# Adafruit_3_5in_480x320_FeatherWing_Capac.net
KiCad netlist of a schematic drawn in EAGLE
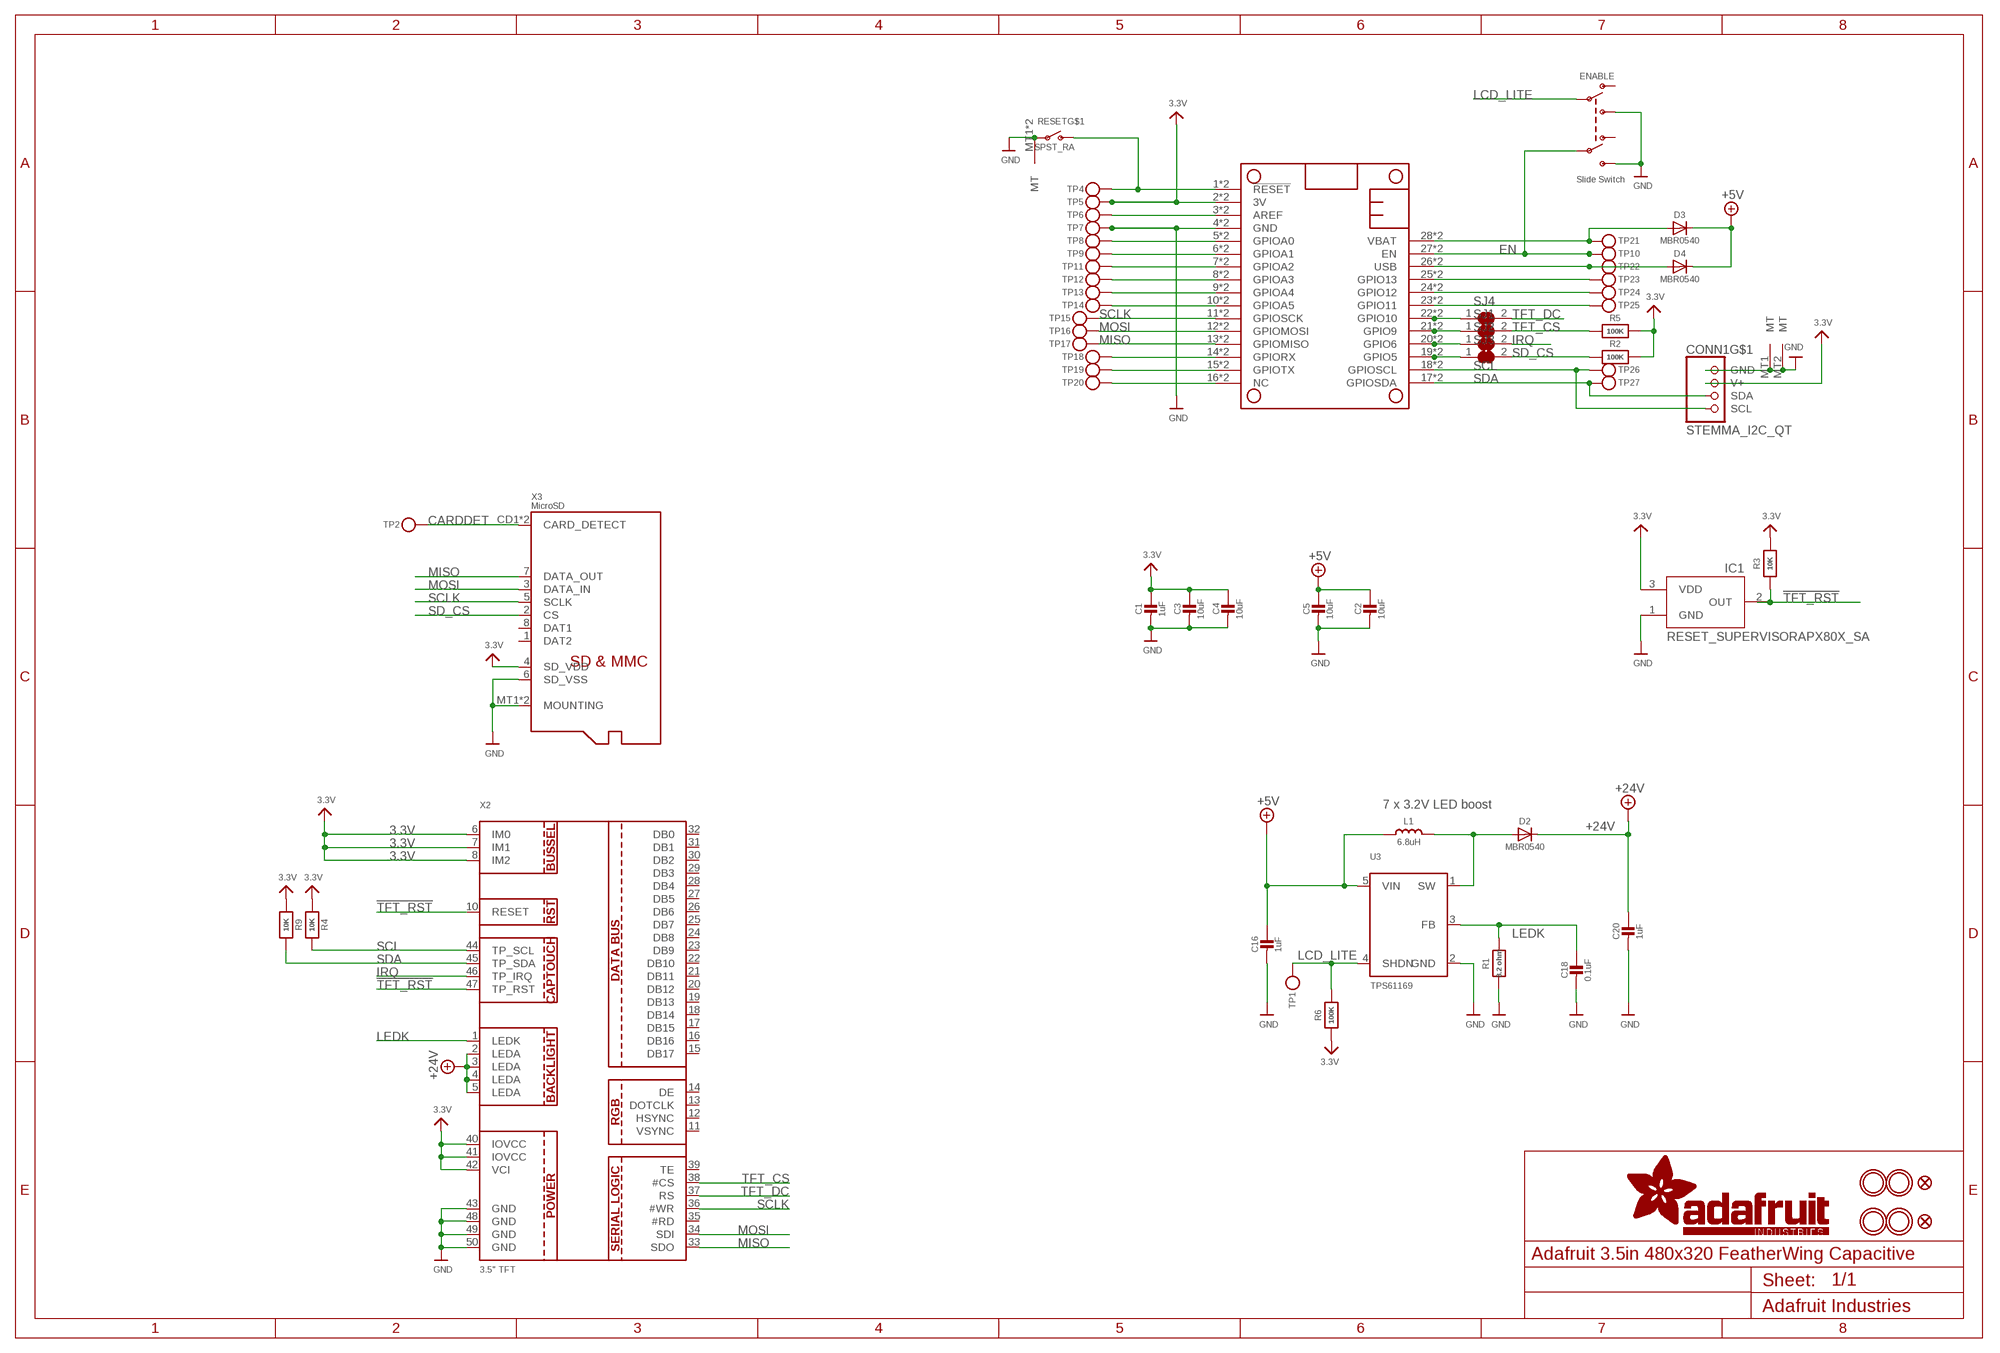
[diagram p0: schematic, sheet 1]

(export (version "E")
  (design (tool "Eeschema 10.0.6"))
  (components
    (comp (ref "C1")
      (value "1uF")
      (footprint "eagle-import:0805-NO")
      (libsource (lib "eagle-import") (part "CAP_CERAMIC0805-NOOUTLINE"))
    )
    (comp (ref "C2")
      (value "10uF")
      (footprint "eagle-import:0805-NO")
      (libsource (lib "eagle-import") (part "CAP_CERAMIC0805-NOOUTLINE"))
    )
    (comp (ref "C3")
      (value "10uF")
      (footprint "eagle-import:0805-NO")
      (libsource (lib "eagle-import") (part "CAP_CERAMIC0805-NOOUTLINE"))
    )
    (comp (ref "C4")
      (value "10uF")
      (footprint "eagle-import:0805-NO")
      (libsource (lib "eagle-import") (part "CAP_CERAMIC0805-NOOUTLINE"))
    )
    (comp (ref "C5")
      (value "10uF")
      (footprint "eagle-import:0805-NO")
      (libsource (lib "eagle-import") (part "CAP_CERAMIC0805-NOOUTLINE"))
    )
    (comp (ref "C16")
      (value "1uF")
      (footprint "eagle-import:0805-NO")
      (libsource (lib "eagle-import") (part "CAP_CERAMIC0805-NOOUTLINE"))
    )
    (comp (ref "C18")
      (value "0.1uF")
      (footprint "eagle-import:0603-NO")
      (libsource (lib "eagle-import") (part "CAP_CERAMIC0603_NO"))
    )
    (comp (ref "C20")
      (value "1uF")
      (footprint "eagle-import:0805-NO")
      (libsource (lib "eagle-import") (part "CAP_CERAMIC0805-NOOUTLINE"))
    )
    (comp (ref "CONN1")
      (value "STEMMA_I2C_QT")
      (footprint "eagle-import:JST_SH4")
      (libsource (lib "eagle-import") (part "STEMMA_I2C_QT"))
    )
    (comp (ref "D2")
      (value "MBR0540")
      (footprint "eagle-import:SOD-123")
      (libsource (lib "eagle-import") (part "DIODESOD-123"))
    )
    (comp (ref "D3")
      (value "MBR0540")
      (footprint "eagle-import:SOD-123")
      (libsource (lib "eagle-import") (part "DIODESOD-123"))
    )
    (comp (ref "D4")
      (value "MBR0540")
      (footprint "eagle-import:SOD-123")
      (libsource (lib "eagle-import") (part "DIODESOD-123"))
    )
    (comp (ref "ENABLE")
      (value "Slide Switch")
      (footprint "eagle-import:EG1390")
      (libsource (lib "eagle-import") (part "SWITCH_DPDTEG1390"))
    )
    (comp (ref "IC1")
      (value "RESET_SUPERVISORAPX80X_SA")
      (footprint "eagle-import:SOT23-WIDE")
      (libsource (lib "eagle-import") (part "RESET_SUPERVISORAPX80X_SA"))
    )
    (comp (ref "L1")
      (value "6.8uH")
      (footprint "eagle-import:INDUCTOR_5X5MM_NR5040_NOTHERMALS")
      (libsource (lib "eagle-import") (part "INDUCTORNR5040"))
    )
    (comp (ref "MS2")
      (value "FEATHERWING_SMTDUAL")
      (footprint "eagle-import:FEATHERWING_SMT2")
      (libsource (lib "eagle-import") (part "FEATHERWING_SMTDUAL"))
    )
    (comp (ref "R1")
      (value "8.2 ohm")
      (footprint "eagle-import:0603-NO")
      (libsource (lib "eagle-import") (part "RESISTOR_0603_NOOUT"))
    )
    (comp (ref "R2")
      (value "100K")
      (footprint "eagle-import:0603-NO")
      (libsource (lib "eagle-import") (part "RESISTOR_0603_NOOUT"))
    )
    (comp (ref "R3")
      (value "10K")
      (footprint "eagle-import:0603-NO")
      (libsource (lib "eagle-import") (part "RESISTOR_0603_NOOUT"))
    )
    (comp (ref "R4")
      (value "10K")
      (footprint "eagle-import:0603-NO")
      (libsource (lib "eagle-import") (part "RESISTOR_0603_NOOUT"))
    )
    (comp (ref "R5")
      (value "100K")
      (footprint "eagle-import:0603-NO")
      (libsource (lib "eagle-import") (part "RESISTOR_0603_NOOUT"))
    )
    (comp (ref "R6")
      (value "100K")
      (footprint "eagle-import:0603-NO")
      (libsource (lib "eagle-import") (part "RESISTOR_0603_NOOUT"))
    )
    (comp (ref "R9")
      (value "10K")
      (footprint "eagle-import:0603-NO")
      (libsource (lib "eagle-import") (part "RESISTOR_0603_NOOUT"))
    )
    (comp (ref "RESET")
      (value "SPST_RA")
      (footprint "eagle-import:SPST_TACTILE_RA")
      (libsource (lib "eagle-import") (part "SWITCH_SPST_MNT_TACT_RA"))
    )
    (comp (ref "SJ1")
      (value "SOLDERJUMPER_CLOSED")
      (footprint "eagle-import:SOLDERJUMPER_CLOSEDWIRE")
      (libsource (lib "eagle-import") (part "SOLDERJUMPER_CLOSED"))
    )
    (comp (ref "SJ2")
      (value "SOLDERJUMPER_CLOSED")
      (footprint "eagle-import:SOLDERJUMPER_CLOSEDWIRE")
      (libsource (lib "eagle-import") (part "SOLDERJUMPER_CLOSED"))
    )
    (comp (ref "SJ3")
      (value "SOLDERJUMPER_CLOSED")
      (footprint "eagle-import:SOLDERJUMPER_CLOSEDWIRE")
      (libsource (lib "eagle-import") (part "SOLDERJUMPER_CLOSED"))
    )
    (comp (ref "SJ4")
      (value "SOLDERJUMPER_CLOSED")
      (footprint "eagle-import:SOLDERJUMPER_CLOSEDWIRE")
      (libsource (lib "eagle-import") (part "SOLDERJUMPER_CLOSED"))
    )
    (comp (ref "TP1")
      (value "TESTPOINTPAD2MM")
      (footprint "eagle-import:TESTPOINT_PAD_2MM")
      (libsource (lib "eagle-import") (part "TESTPOINTPAD2MM"))
    )
    (comp (ref "TP2")
      (value "TESTPOINTPAD2MM")
      (footprint "eagle-import:TESTPOINT_PAD_2MM")
      (libsource (lib "eagle-import") (part "TESTPOINTPAD2MM"))
    )
    (comp (ref "TP4")
      (value "TESTPOINTPAD2MM")
      (footprint "eagle-import:TESTPOINT_PAD_2MM")
      (libsource (lib "eagle-import") (part "TESTPOINTPAD2MM"))
    )
    (comp (ref "TP5")
      (value "TESTPOINTPAD2MM")
      (footprint "eagle-import:TESTPOINT_PAD_2MM")
      (libsource (lib "eagle-import") (part "TESTPOINTPAD2MM"))
    )
    (comp (ref "TP6")
      (value "TESTPOINTPAD2MM")
      (footprint "eagle-import:TESTPOINT_PAD_2MM")
      (libsource (lib "eagle-import") (part "TESTPOINTPAD2MM"))
    )
    (comp (ref "TP7")
      (value "TESTPOINTPAD2MM")
      (footprint "eagle-import:TESTPOINT_PAD_2MM")
      (libsource (lib "eagle-import") (part "TESTPOINTPAD2MM"))
    )
    (comp (ref "TP8")
      (value "TESTPOINTPAD2MM")
      (footprint "eagle-import:TESTPOINT_PAD_2MM")
      (libsource (lib "eagle-import") (part "TESTPOINTPAD2MM"))
    )
    (comp (ref "TP9")
      (value "TESTPOINTPAD2MM")
      (footprint "eagle-import:TESTPOINT_PAD_2MM")
      (libsource (lib "eagle-import") (part "TESTPOINTPAD2MM"))
    )
    (comp (ref "TP10")
      (value "TESTPOINTPAD2MM")
      (footprint "eagle-import:TESTPOINT_PAD_2MM")
      (libsource (lib "eagle-import") (part "TESTPOINTPAD2MM"))
    )
    (comp (ref "TP11")
      (value "TESTPOINTPAD2MM")
      (footprint "eagle-import:TESTPOINT_PAD_2MM")
      (libsource (lib "eagle-import") (part "TESTPOINTPAD2MM"))
    )
    (comp (ref "TP12")
      (value "TESTPOINTPAD2MM")
      (footprint "eagle-import:TESTPOINT_PAD_2MM")
      (libsource (lib "eagle-import") (part "TESTPOINTPAD2MM"))
    )
    (comp (ref "TP13")
      (value "TESTPOINTPAD2MM")
      (footprint "eagle-import:TESTPOINT_PAD_2MM")
      (libsource (lib "eagle-import") (part "TESTPOINTPAD2MM"))
    )
    (comp (ref "TP14")
      (value "TESTPOINTPAD2MM")
      (footprint "eagle-import:TESTPOINT_PAD_2MM")
      (libsource (lib "eagle-import") (part "TESTPOINTPAD2MM"))
    )
    (comp (ref "TP15")
      (value "TESTPOINTPAD2MM")
      (footprint "eagle-import:TESTPOINT_PAD_2MM")
      (libsource (lib "eagle-import") (part "TESTPOINTPAD2MM"))
    )
    (comp (ref "TP16")
      (value "TESTPOINTPAD2MM")
      (footprint "eagle-import:TESTPOINT_PAD_2MM")
      (libsource (lib "eagle-import") (part "TESTPOINTPAD2MM"))
    )
    (comp (ref "TP17")
      (value "TESTPOINTPAD2MM")
      (footprint "eagle-import:TESTPOINT_PAD_2MM")
      (libsource (lib "eagle-import") (part "TESTPOINTPAD2MM"))
    )
    (comp (ref "TP18")
      (value "TESTPOINTPAD2MM")
      (footprint "eagle-import:TESTPOINT_PAD_2MM")
      (libsource (lib "eagle-import") (part "TESTPOINTPAD2MM"))
    )
    (comp (ref "TP19")
      (value "TESTPOINTPAD2MM")
      (footprint "eagle-import:TESTPOINT_PAD_2MM")
      (libsource (lib "eagle-import") (part "TESTPOINTPAD2MM"))
    )
    (comp (ref "TP20")
      (value "TESTPOINTPAD2MM")
      (footprint "eagle-import:TESTPOINT_PAD_2MM")
      (libsource (lib "eagle-import") (part "TESTPOINTPAD2MM"))
    )
    (comp (ref "TP21")
      (value "TESTPOINTPAD2MM")
      (footprint "eagle-import:TESTPOINT_PAD_2MM")
      (libsource (lib "eagle-import") (part "TESTPOINTPAD2MM"))
    )
    (comp (ref "TP22")
      (value "TESTPOINTPAD2MM")
      (footprint "eagle-import:TESTPOINT_PAD_2MM")
      (libsource (lib "eagle-import") (part "TESTPOINTPAD2MM"))
    )
    (comp (ref "TP23")
      (value "TESTPOINTPAD2MM")
      (footprint "eagle-import:TESTPOINT_PAD_2MM")
      (libsource (lib "eagle-import") (part "TESTPOINTPAD2MM"))
    )
    (comp (ref "TP24")
      (value "TESTPOINTPAD2MM")
      (footprint "eagle-import:TESTPOINT_PAD_2MM")
      (libsource (lib "eagle-import") (part "TESTPOINTPAD2MM"))
    )
    (comp (ref "TP25")
      (value "TESTPOINTPAD2MM")
      (footprint "eagle-import:TESTPOINT_PAD_2MM")
      (libsource (lib "eagle-import") (part "TESTPOINTPAD2MM"))
    )
    (comp (ref "TP26")
      (value "TESTPOINTPAD2MM")
      (footprint "eagle-import:TESTPOINT_PAD_2MM")
      (libsource (lib "eagle-import") (part "TESTPOINTPAD2MM"))
    )
    (comp (ref "TP27")
      (value "TESTPOINTPAD2MM")
      (footprint "eagle-import:TESTPOINT_PAD_2MM")
      (libsource (lib "eagle-import") (part "TESTPOINTPAD2MM"))
    )
    (comp (ref "U$7")
      (value "MOUNTINGHOLE3.0THIN")
      (footprint "eagle-import:MOUNTINGHOLE_3.0_PLATEDTHIN")
      (libsource (lib "eagle-import") (part "MOUNTINGHOLE3.0THIN"))
    )
    (comp (ref "U$9")
      (value "FIDUCIAL_1MM")
      (footprint "eagle-import:FIDUCIAL_1MM")
      (libsource (lib "eagle-import") (part "FIDUCIAL_1MM"))
    )
    (comp (ref "U$15")
      (value "MOUNTINGHOLE3.0THIN")
      (footprint "eagle-import:MOUNTINGHOLE_3.0_PLATEDTHIN")
      (libsource (lib "eagle-import") (part "MOUNTINGHOLE3.0THIN"))
    )
    (comp (ref "U$16")
      (value "MOUNTINGHOLE3.0THIN")
      (footprint "eagle-import:MOUNTINGHOLE_3.0_PLATEDTHIN")
      (libsource (lib "eagle-import") (part "MOUNTINGHOLE3.0THIN"))
    )
    (comp (ref "U$17")
      (value "MOUNTINGHOLE3.0THIN")
      (footprint "eagle-import:MOUNTINGHOLE_3.0_PLATEDTHIN")
      (libsource (lib "eagle-import") (part "MOUNTINGHOLE3.0THIN"))
    )
    (comp (ref "U$23")
      (value "FIDUCIAL_1MM")
      (footprint "eagle-import:FIDUCIAL_1MM")
      (libsource (lib "eagle-import") (part "FIDUCIAL_1MM"))
    )
    (comp (ref "U3")
      (value "TPS61169")
      (footprint "eagle-import:SC70-5")
      (libsource (lib "eagle-import") (part "VREG_BOOST_5PIN_SC70"))
    )
    (comp (ref "X2")
      (value "3.5\" TFT")
      (footprint "eagle-import:TFT_3.5IN_320X480_50PIN")
      (libsource (lib "eagle-import") (part "DISP_LCD_3.5IN_320X480CTP_50PIN"))
    )
    (comp (ref "X3")
      (value "MicroSD")
      (footprint "eagle-import:MICROSD")
      (libsource (lib "eagle-import") (part "MICROSD"))
    )
  )
  (nets
    (net (code "1") (name "+5V") (class "Default")
      (node (ref "C16") (pin "1") (pinfunction "1_1") (pintype "passive"))
      (node (ref "C2") (pin "1") (pinfunction "1_1") (pintype "passive"))
      (node (ref "C5") (pin "1") (pinfunction "1_1") (pintype "passive"))
      (node (ref "D3") (pin "C") (pinfunction "C_C") (pintype "passive"))
      (node (ref "D4") (pin "C") (pinfunction "C_C") (pintype "passive"))
      (node (ref "L1") (pin "P$1") (pinfunction "1_P$1") (pintype "passive"))
      (node (ref "U3") (pin "5") (pinfunction "VIN_5") (pintype "bidirectional"))
    )
    (net (code "2") (name "+24V") (class "Default")
      (node (ref "C20") (pin "1") (pinfunction "1_1") (pintype "passive"))
      (node (ref "D2") (pin "C") (pinfunction "C_C") (pintype "passive"))
      (node (ref "X2") (pin "2") (pinfunction "LEDA_2") (pintype "bidirectional"))
      (node (ref "X2") (pin "3") (pinfunction "LEDA_3") (pintype "bidirectional"))
      (node (ref "X2") (pin "4") (pinfunction "LEDA_4") (pintype "bidirectional"))
      (node (ref "X2") (pin "5") (pinfunction "LEDA_5") (pintype "bidirectional"))
    )
    (net (code "3") (name "/CARDDET") (class "Default")
      (node (ref "TP2") (pin "P$1") (pinfunction "P$1_P$1") (pintype "bidirectional"))
      (node (ref "X3") (pin "CD1") (pinfunction "CARD_DETECT_CD1") (pintype "passive"))
      (node (ref "X3") (pin "CD2") (pinfunction "CARD_DETECT_CD2") (pintype "passive"))
    )
    (net (code "4") (name "/EN") (class "Default")
      (node (ref "ENABLE") (pin "P2") (pinfunction "P2_P2") (pintype "passive"))
      (node (ref "MS2") (pin "27") (pinfunction "EN_27") (pintype "passive"))
      (node (ref "MS2") (pin "27'") (pinfunction "EN_27'") (pintype "passive"))
      (node (ref "TP10") (pin "P$1") (pinfunction "P$1_P$1") (pintype "bidirectional"))
    )
    (net (code "5") (name "/IRQ") (class "Default")
      (node (ref "SJ2") (pin "2") (pinfunction "2_2") (pintype "passive"))
      (node (ref "X2") (pin "46") (pinfunction "TP_IRQ_46") (pintype "bidirectional"))
    )
    (net (code "6") (name "/LCD_LITE") (class "Default")
      (node (ref "ENABLE") (pin "P1") (pinfunction "P1_P1") (pintype "passive"))
      (node (ref "R6") (pin "2") (pinfunction "2_2") (pintype "passive"))
      (node (ref "TP1") (pin "P$1") (pinfunction "P$1_P$1") (pintype "bidirectional"))
      (node (ref "U3") (pin "4") (pinfunction "SHDN_4") (pintype "bidirectional"))
    )
    (net (code "7") (name "/LEDK") (class "Default")
      (node (ref "C18") (pin "1") (pinfunction "1_1") (pintype "passive"))
      (node (ref "R1") (pin "2") (pinfunction "2_2") (pintype "passive"))
      (node (ref "U3") (pin "3") (pinfunction "FB_3") (pintype "bidirectional"))
      (node (ref "X2") (pin "1") (pinfunction "LEDK_1") (pintype "bidirectional"))
    )
    (net (code "8") (name "/MISO") (class "Default")
      (node (ref "MS2") (pin "13") (pinfunction "GPIOMISO_13") (pintype "bidirectional"))
      (node (ref "MS2") (pin "13'") (pinfunction "GPIOMISO_13'") (pintype "bidirectional"))
      (node (ref "TP17") (pin "P$1") (pinfunction "P$1_P$1") (pintype "bidirectional"))
      (node (ref "X2") (pin "33") (pinfunction "SDO_33") (pintype "bidirectional"))
      (node (ref "X3") (pin "7") (pinfunction "DATA_OUT_7") (pintype "output"))
    )
    (net (code "9") (name "/MOSI") (class "Default")
      (node (ref "MS2") (pin "12") (pinfunction "GPIOMOSI_12") (pintype "bidirectional"))
      (node (ref "MS2") (pin "12'") (pinfunction "GPIOMOSI_12'") (pintype "bidirectional"))
      (node (ref "TP16") (pin "P$1") (pinfunction "P$1_P$1") (pintype "bidirectional"))
      (node (ref "X2") (pin "34") (pinfunction "SDI_34") (pintype "bidirectional"))
      (node (ref "X3") (pin "3") (pinfunction "DATA_IN_3") (pintype "input"))
    )
    (net (code "10") (name "/SCL") (class "Default")
      (node (ref "CONN1") (pin "4") (pinfunction "SCL_4") (pintype "passive"))
      (node (ref "MS2") (pin "18") (pinfunction "GPIOSCL_18") (pintype "bidirectional"))
      (node (ref "MS2") (pin "18'") (pinfunction "GPIOSCL_18'") (pintype "bidirectional"))
      (node (ref "R4") (pin "2") (pinfunction "2_2") (pintype "passive"))
      (node (ref "TP26") (pin "P$1") (pinfunction "P$1_P$1") (pintype "bidirectional"))
      (node (ref "X2") (pin "44") (pinfunction "TP_SCL_44") (pintype "bidirectional"))
    )
    (net (code "11") (name "/SCLK") (class "Default")
      (node (ref "MS2") (pin "11") (pinfunction "GPIOSCK_11") (pintype "bidirectional"))
      (node (ref "MS2") (pin "11'") (pinfunction "GPIOSCK_11'") (pintype "bidirectional"))
      (node (ref "TP15") (pin "P$1") (pinfunction "P$1_P$1") (pintype "bidirectional"))
      (node (ref "X2") (pin "36") (pinfunction "#WR_36") (pintype "bidirectional"))
      (node (ref "X3") (pin "5") (pinfunction "SCLK_5") (pintype "input"))
    )
    (net (code "12") (name "/SDA") (class "Default")
      (node (ref "CONN1") (pin "3") (pinfunction "SDA_3") (pintype "passive"))
      (node (ref "MS2") (pin "17") (pinfunction "GPIOSDA_17") (pintype "bidirectional"))
      (node (ref "MS2") (pin "17'") (pinfunction "GPIOSDA_17'") (pintype "bidirectional"))
      (node (ref "R9") (pin "2") (pinfunction "2_2") (pintype "passive"))
      (node (ref "TP27") (pin "P$1") (pinfunction "P$1_P$1") (pintype "bidirectional"))
      (node (ref "X2") (pin "45") (pinfunction "TP_SDA_45") (pintype "bidirectional"))
    )
    (net (code "13") (name "/SD_CS") (class "Default")
      (node (ref "R2") (pin "1") (pinfunction "1_1") (pintype "passive"))
      (node (ref "SJ3") (pin "2") (pinfunction "2_2") (pintype "passive"))
      (node (ref "X3") (pin "2") (pinfunction "CS_2") (pintype "input"))
    )
    (net (code "14") (name "/TFT_CS") (class "Default")
      (node (ref "R5") (pin "1") (pinfunction "1_1") (pintype "passive"))
      (node (ref "SJ1") (pin "2") (pinfunction "2_2") (pintype "passive"))
      (node (ref "X2") (pin "38") (pinfunction "#CS_38") (pintype "bidirectional"))
    )
    (net (code "15") (name "/TFT_DC") (class "Default")
      (node (ref "SJ4") (pin "2") (pinfunction "2_2") (pintype "passive"))
      (node (ref "X2") (pin "37") (pinfunction "RS_37") (pintype "bidirectional"))
    )
    (net (code "16") (name "/~{TFT_RST}") (class "Default")
      (node (ref "IC1") (pin "2") (pinfunction "OUT_2") (pintype "output"))
      (node (ref "R3") (pin "1") (pinfunction "1_1") (pintype "passive"))
      (node (ref "X2") (pin "10") (pinfunction "RESET_10") (pintype "bidirectional"))
      (node (ref "X2") (pin "47") (pinfunction "TP_RST_47") (pintype "bidirectional"))
    )
    (net (code "17") (name "3.3V") (class "Default")
      (node (ref "C1") (pin "1") (pinfunction "1_1") (pintype "passive"))
      (node (ref "C3") (pin "1") (pinfunction "1_1") (pintype "passive"))
      (node (ref "C4") (pin "1") (pinfunction "1_1") (pintype "passive"))
      (node (ref "CONN1") (pin "2") (pinfunction "V+_2") (pintype "passive"))
      (node (ref "IC1") (pin "3") (pinfunction "VDD_3") (pintype "power_in"))
      (node (ref "MS2") (pin "2") (pinfunction "3V_2") (pintype "power_in"))
      (node (ref "MS2") (pin "2'") (pinfunction "3V_2'") (pintype "power_in"))
      (node (ref "R2") (pin "2") (pinfunction "2_2") (pintype "passive"))
      (node (ref "R3") (pin "2") (pinfunction "2_2") (pintype "passive"))
      (node (ref "R4") (pin "1") (pinfunction "1_1") (pintype "passive"))
      (node (ref "R5") (pin "2") (pinfunction "2_2") (pintype "passive"))
      (node (ref "R6") (pin "1") (pinfunction "1_1") (pintype "passive"))
      (node (ref "R9") (pin "1") (pinfunction "1_1") (pintype "passive"))
      (node (ref "TP5") (pin "P$1") (pinfunction "P$1_P$1") (pintype "bidirectional"))
      (node (ref "X2") (pin "40") (pinfunction "IOVCC_40") (pintype "bidirectional"))
      (node (ref "X2") (pin "41") (pinfunction "IOVCC_41") (pintype "bidirectional"))
      (node (ref "X2") (pin "42") (pinfunction "VCI_42") (pintype "bidirectional"))
      (node (ref "X2") (pin "6") (pinfunction "IM0_6") (pintype "bidirectional"))
      (node (ref "X2") (pin "7") (pinfunction "IM1_7") (pintype "bidirectional"))
      (node (ref "X2") (pin "8") (pinfunction "IM2_8") (pintype "bidirectional"))
      (node (ref "X3") (pin "4") (pinfunction "SD_VDD_4") (pintype "power_in"))
    )
    (net (code "18") (name "GND") (class "Default")
      (node (ref "C1") (pin "2") (pinfunction "2_2") (pintype "passive"))
      (node (ref "C16") (pin "2") (pinfunction "2_2") (pintype "passive"))
      (node (ref "C18") (pin "2") (pinfunction "2_2") (pintype "passive"))
      (node (ref "C2") (pin "2") (pinfunction "2_2") (pintype "passive"))
      (node (ref "C20") (pin "2") (pinfunction "2_2") (pintype "passive"))
      (node (ref "C3") (pin "2") (pinfunction "2_2") (pintype "passive"))
      (node (ref "C4") (pin "2") (pinfunction "2_2") (pintype "passive"))
      (node (ref "C5") (pin "2") (pinfunction "2_2") (pintype "passive"))
      (node (ref "CONN1") (pin "1") (pinfunction "GND_1") (pintype "passive"))
      (node (ref "CONN1") (pin "MT1") (pinfunction "MT_MT1") (pintype "bidirectional"))
      (node (ref "CONN1") (pin "MT2") (pinfunction "MT_MT2") (pintype "bidirectional"))
      (node (ref "ENABLE") (pin "S1") (pinfunction "S1_S1") (pintype "passive"))
      (node (ref "ENABLE") (pin "S2") (pinfunction "S2_S2") (pintype "passive"))
      (node (ref "IC1") (pin "1") (pinfunction "GND_1") (pintype "power_in"))
      (node (ref "MS2") (pin "4") (pinfunction "GND_4") (pintype "power_in"))
      (node (ref "MS2") (pin "4'") (pinfunction "GND_4'") (pintype "power_in"))
      (node (ref "R1") (pin "1") (pinfunction "1_1") (pintype "passive"))
      (node (ref "RESET") (pin "1") (pinfunction "P_1") (pintype "passive"))
      (node (ref "RESET") (pin "MT1") (pinfunction "MT_MT1") (pintype "bidirectional"))
      (node (ref "RESET") (pin "MT2") (pinfunction "MT_MT2") (pintype "bidirectional"))
      (node (ref "TP7") (pin "P$1") (pinfunction "P$1_P$1") (pintype "bidirectional"))
      (node (ref "U3") (pin "2") (pinfunction "GND_2") (pintype "bidirectional"))
      (node (ref "X2") (pin "43") (pinfunction "GND_43") (pintype "bidirectional"))
      (node (ref "X2") (pin "48") (pinfunction "GND_48") (pintype "bidirectional"))
      (node (ref "X2") (pin "49") (pinfunction "GND_49") (pintype "bidirectional"))
      (node (ref "X2") (pin "50") (pinfunction "GND_50") (pintype "bidirectional"))
      (node (ref "X3") (pin "6") (pinfunction "SD_VSS_6") (pintype "power_in"))
      (node (ref "X3") (pin "MT1") (pinfunction "MOUNTING_MT1") (pintype "passive"))
      (node (ref "X3") (pin "MT2") (pinfunction "MOUNTING_MT2") (pintype "passive"))
    )
    (net (code "19") (name "Net-(D3-PadA)") (class "Default")
      (node (ref "D3") (pin "A") (pinfunction "A_A") (pintype "passive"))
      (node (ref "MS2") (pin "28") (pinfunction "VBAT_28") (pintype "power_in"))
      (node (ref "MS2") (pin "28'") (pinfunction "VBAT_28'") (pintype "power_in"))
      (node (ref "TP21") (pin "P$1") (pinfunction "P$1_P$1") (pintype "bidirectional"))
    )
    (net (code "20") (name "Net-(D4-PadA)") (class "Default")
      (node (ref "D4") (pin "A") (pinfunction "A_A") (pintype "passive"))
      (node (ref "MS2") (pin "26") (pinfunction "USB_26") (pintype "power_in"))
      (node (ref "MS2") (pin "26'") (pinfunction "USB_26'") (pintype "power_in"))
      (node (ref "TP22") (pin "P$1") (pinfunction "P$1_P$1") (pintype "bidirectional"))
    )
    (net (code "21") (name "Net-(L1-2)") (class "Default")
      (node (ref "D2") (pin "A") (pinfunction "A_A") (pintype "passive"))
      (node (ref "L1") (pin "P$2") (pinfunction "2_P$2") (pintype "passive"))
      (node (ref "U3") (pin "1") (pinfunction "SW_1") (pintype "bidirectional"))
    )
    (net (code "22") (name "Net-(MS2-AREF-Pad3')") (class "Default")
      (node (ref "MS2") (pin "3") (pinfunction "AREF_3") (pintype "passive"))
      (node (ref "MS2") (pin "3'") (pinfunction "AREF_3'") (pintype "passive"))
      (node (ref "TP6") (pin "P$1") (pinfunction "P$1_P$1") (pintype "bidirectional"))
    )
    (net (code "23") (name "Net-(MS2-GPIO5-Pad19')") (class "Default")
      (node (ref "MS2") (pin "19") (pinfunction "GPIO5_19") (pintype "bidirectional"))
      (node (ref "MS2") (pin "19'") (pinfunction "GPIO5_19'") (pintype "bidirectional"))
      (node (ref "SJ3") (pin "1") (pinfunction "1_1") (pintype "passive"))
    )
    (net (code "24") (name "Net-(MS2-GPIO6-Pad20')") (class "Default")
      (node (ref "MS2") (pin "20") (pinfunction "GPIO6_20") (pintype "bidirectional"))
      (node (ref "MS2") (pin "20'") (pinfunction "GPIO6_20'") (pintype "bidirectional"))
      (node (ref "SJ2") (pin "1") (pinfunction "1_1") (pintype "passive"))
    )
    (net (code "25") (name "Net-(MS2-GPIO9-Pad21')") (class "Default")
      (node (ref "MS2") (pin "21") (pinfunction "GPIO9_21") (pintype "bidirectional"))
      (node (ref "MS2") (pin "21'") (pinfunction "GPIO9_21'") (pintype "bidirectional"))
      (node (ref "SJ1") (pin "1") (pinfunction "1_1") (pintype "passive"))
    )
    (net (code "26") (name "Net-(MS2-GPIO10-Pad22')") (class "Default")
      (node (ref "MS2") (pin "22") (pinfunction "GPIO10_22") (pintype "bidirectional"))
      (node (ref "MS2") (pin "22'") (pinfunction "GPIO10_22'") (pintype "bidirectional"))
      (node (ref "SJ4") (pin "1") (pinfunction "1_1") (pintype "passive"))
    )
    (net (code "27") (name "Net-(MS2-GPIO11-Pad23')") (class "Default")
      (node (ref "MS2") (pin "23") (pinfunction "GPIO11_23") (pintype "bidirectional"))
      (node (ref "MS2") (pin "23'") (pinfunction "GPIO11_23'") (pintype "bidirectional"))
      (node (ref "TP25") (pin "P$1") (pinfunction "P$1_P$1") (pintype "bidirectional"))
    )
    (net (code "28") (name "Net-(MS2-GPIO12-Pad24')") (class "Default")
      (node (ref "MS2") (pin "24") (pinfunction "GPIO12_24") (pintype "bidirectional"))
      (node (ref "MS2") (pin "24'") (pinfunction "GPIO12_24'") (pintype "bidirectional"))
      (node (ref "TP24") (pin "P$1") (pinfunction "P$1_P$1") (pintype "bidirectional"))
    )
    (net (code "29") (name "Net-(MS2-GPIO13-Pad25')") (class "Default")
      (node (ref "MS2") (pin "25") (pinfunction "GPIO13_25") (pintype "bidirectional"))
      (node (ref "MS2") (pin "25'") (pinfunction "GPIO13_25'") (pintype "bidirectional"))
      (node (ref "TP23") (pin "P$1") (pinfunction "P$1_P$1") (pintype "bidirectional"))
    )
    (net (code "30") (name "Net-(MS2-GPIOA0-Pad5')") (class "Default")
      (node (ref "MS2") (pin "5") (pinfunction "GPIOA0_5") (pintype "bidirectional"))
      (node (ref "MS2") (pin "5'") (pinfunction "GPIOA0_5'") (pintype "bidirectional"))
      (node (ref "TP8") (pin "P$1") (pinfunction "P$1_P$1") (pintype "bidirectional"))
    )
    (net (code "31") (name "Net-(MS2-GPIOA1-Pad6')") (class "Default")
      (node (ref "MS2") (pin "6") (pinfunction "GPIOA1_6") (pintype "bidirectional"))
      (node (ref "MS2") (pin "6'") (pinfunction "GPIOA1_6'") (pintype "bidirectional"))
      (node (ref "TP9") (pin "P$1") (pinfunction "P$1_P$1") (pintype "bidirectional"))
    )
    (net (code "32") (name "Net-(MS2-GPIOA2-Pad7')") (class "Default")
      (node (ref "MS2") (pin "7") (pinfunction "GPIOA2_7") (pintype "bidirectional"))
      (node (ref "MS2") (pin "7'") (pinfunction "GPIOA2_7'") (pintype "bidirectional"))
      (node (ref "TP11") (pin "P$1") (pinfunction "P$1_P$1") (pintype "bidirectional"))
    )
    (net (code "33") (name "Net-(MS2-GPIOA3-Pad8')") (class "Default")
      (node (ref "MS2") (pin "8") (pinfunction "GPIOA3_8") (pintype "bidirectional"))
      (node (ref "MS2") (pin "8'") (pinfunction "GPIOA3_8'") (pintype "bidirectional"))
      (node (ref "TP12") (pin "P$1") (pinfunction "P$1_P$1") (pintype "bidirectional"))
    )
    (net (code "34") (name "Net-(MS2-GPIOA4-Pad9')") (class "Default")
      (node (ref "MS2") (pin "9") (pinfunction "GPIOA4_9") (pintype "bidirectional"))
      (node (ref "MS2") (pin "9'") (pinfunction "GPIOA4_9'") (pintype "bidirectional"))
      (node (ref "TP13") (pin "P$1") (pinfunction "P$1_P$1") (pintype "bidirectional"))
    )
    (net (code "35") (name "Net-(MS2-GPIOA5-Pad10')") (class "Default")
      (node (ref "MS2") (pin "10") (pinfunction "GPIOA5_10") (pintype "bidirectional"))
      (node (ref "MS2") (pin "10'") (pinfunction "GPIOA5_10'") (pintype "bidirectional"))
      (node (ref "TP14") (pin "P$1") (pinfunction "P$1_P$1") (pintype "bidirectional"))
    )
    (net (code "36") (name "Net-(MS2-GPIORX-Pad14')") (class "Default")
      (node (ref "MS2") (pin "14") (pinfunction "GPIORX_14") (pintype "bidirectional"))
      (node (ref "MS2") (pin "14'") (pinfunction "GPIORX_14'") (pintype "bidirectional"))
      (node (ref "TP18") (pin "P$1") (pinfunction "P$1_P$1") (pintype "bidirectional"))
    )
    (net (code "37") (name "Net-(MS2-GPIOTX-Pad15')") (class "Default")
      (node (ref "MS2") (pin "15") (pinfunction "GPIOTX_15") (pintype "bidirectional"))
      (node (ref "MS2") (pin "15'") (pinfunction "GPIOTX_15'") (pintype "bidirectional"))
      (node (ref "TP19") (pin "P$1") (pinfunction "P$1_P$1") (pintype "bidirectional"))
    )
    (net (code "38") (name "Net-(MS2-NC-Pad16')") (class "Default")
      (node (ref "MS2") (pin "16") (pinfunction "NC_16") (pintype "passive"))
      (node (ref "MS2") (pin "16'") (pinfunction "NC_16'") (pintype "passive"))
      (node (ref "TP20") (pin "P$1") (pinfunction "P$1_P$1") (pintype "bidirectional"))
    )
    (net (code "39") (name "Net-(RESETA-S)") (class "Default")
      (node (ref "MS2") (pin "1") (pinfunction "~{RESET}_1") (pintype "input"))
      (node (ref "MS2") (pin "1'") (pinfunction "~{RESET}_1'") (pintype "input"))
      (node (ref "RESET") (pin "2") (pinfunction "S_2") (pintype "passive"))
      (node (ref "TP4") (pin "P$1") (pinfunction "P$1_P$1") (pintype "bidirectional"))
    )
    (net (code "40") (name "unconnected-(ENABLE-PadO1)") (class "Default")
      (node (ref "ENABLE") (pin "O1") (pinfunction "O1_O1") (pintype "passive"))
    )
    (net (code "41") (name "unconnected-(ENABLE-PadO2)") (class "Default")
      (node (ref "ENABLE") (pin "O2") (pinfunction "O2_O2") (pintype "passive"))
    )
    (net (code "42") (name "unconnected-(X2-#RD-Pad35)") (class "Default")
      (node (ref "X2") (pin "35") (pinfunction "#RD_35") (pintype "bidirectional"))
    )
    (net (code "43") (name "unconnected-(X2-DB0-Pad32)") (class "Default")
      (node (ref "X2") (pin "32") (pinfunction "DB0_32") (pintype "bidirectional"))
    )
    (net (code "44") (name "unconnected-(X2-DB1-Pad31)") (class "Default")
      (node (ref "X2") (pin "31") (pinfunction "DB1_31") (pintype "bidirectional"))
    )
    (net (code "45") (name "unconnected-(X2-DB2-Pad30)") (class "Default")
      (node (ref "X2") (pin "30") (pinfunction "DB2_30") (pintype "bidirectional"))
    )
    (net (code "46") (name "unconnected-(X2-DB3-Pad29)") (class "Default")
      (node (ref "X2") (pin "29") (pinfunction "DB3_29") (pintype "bidirectional"))
    )
    (net (code "47") (name "unconnected-(X2-DB4-Pad28)") (class "Default")
      (node (ref "X2") (pin "28") (pinfunction "DB4_28") (pintype "bidirectional"))
    )
    (net (code "48") (name "unconnected-(X2-DB5-Pad27)") (class "Default")
      (node (ref "X2") (pin "27") (pinfunction "DB5_27") (pintype "bidirectional"))
    )
    (net (code "49") (name "unconnected-(X2-DB6-Pad26)") (class "Default")
      (node (ref "X2") (pin "26") (pinfunction "DB6_26") (pintype "bidirectional"))
    )
    (net (code "50") (name "unconnected-(X2-DB7-Pad25)") (class "Default")
      (node (ref "X2") (pin "25") (pinfunction "DB7_25") (pintype "bidirectional"))
    )
    (net (code "51") (name "unconnected-(X2-DB8-Pad24)") (class "Default")
      (node (ref "X2") (pin "24") (pinfunction "DB8_24") (pintype "bidirectional"))
    )
    (net (code "52") (name "unconnected-(X2-DB9-Pad23)") (class "Default")
      (node (ref "X2") (pin "23") (pinfunction "DB9_23") (pintype "bidirectional"))
    )
    (net (code "53") (name "unconnected-(X2-DB10-Pad22)") (class "Default")
      (node (ref "X2") (pin "22") (pinfunction "DB10_22") (pintype "bidirectional"))
    )
    (net (code "54") (name "unconnected-(X2-DB11-Pad21)") (class "Default")
      (node (ref "X2") (pin "21") (pinfunction "DB11_21") (pintype "bidirectional"))
    )
    (net (code "55") (name "unconnected-(X2-DB12-Pad20)") (class "Default")
      (node (ref "X2") (pin "20") (pinfunction "DB12_20") (pintype "bidirectional"))
    )
    (net (code "56") (name "unconnected-(X2-DB13-Pad19)") (class "Default")
      (node (ref "X2") (pin "19") (pinfunction "DB13_19") (pintype "bidirectional"))
    )
    (net (code "57") (name "unconnected-(X2-DB14-Pad18)") (class "Default")
      (node (ref "X2") (pin "18") (pinfunction "DB14_18") (pintype "bidirectional"))
    )
    (net (code "58") (name "unconnected-(X2-DB15-Pad17)") (class "Default")
      (node (ref "X2") (pin "17") (pinfunction "DB15_17") (pintype "bidirectional"))
    )
    (net (code "59") (name "unconnected-(X2-DB16-Pad16)") (class "Default")
      (node (ref "X2") (pin "16") (pinfunction "DB16_16") (pintype "bidirectional"))
    )
    (net (code "60") (name "unconnected-(X2-DB17-Pad15)") (class "Default")
      (node (ref "X2") (pin "15") (pinfunction "DB17_15") (pintype "bidirectional"))
    )
    (net (code "61") (name "unconnected-(X2-DE-Pad14)") (class "Default")
      (node (ref "X2") (pin "14") (pinfunction "DE_14") (pintype "bidirectional"))
    )
    (net (code "62") (name "unconnected-(X2-DOTCLK-Pad13)") (class "Default")
      (node (ref "X2") (pin "13") (pinfunction "DOTCLK_13") (pintype "bidirectional"))
    )
    (net (code "63") (name "unconnected-(X2-HSYNC-Pad12)") (class "Default")
      (node (ref "X2") (pin "12") (pinfunction "HSYNC_12") (pintype "bidirectional"))
    )
    (net (code "64") (name "unconnected-(X2-TE-Pad39)") (class "Default")
      (node (ref "X2") (pin "39") (pinfunction "TE_39") (pintype "bidirectional"))
    )
    (net (code "65") (name "unconnected-(X2-VSYNC-Pad11)") (class "Default")
      (node (ref "X2") (pin "11") (pinfunction "VSYNC_11") (pintype "bidirectional"))
    )
    (net (code "66") (name "unconnected-(X3-DAT1-Pad8)") (class "Default")
      (node (ref "X3") (pin "8") (pinfunction "DAT1_8") (pintype "bidirectional"))
    )
    (net (code "67") (name "unconnected-(X3-DAT2-Pad1)") (class "Default")
      (node (ref "X3") (pin "1") (pinfunction "DAT2_1") (pintype "bidirectional"))
    )
  )
)
